# 08_Peripherals.net
KiCad netlist of a schematic drawn in Altium Designer
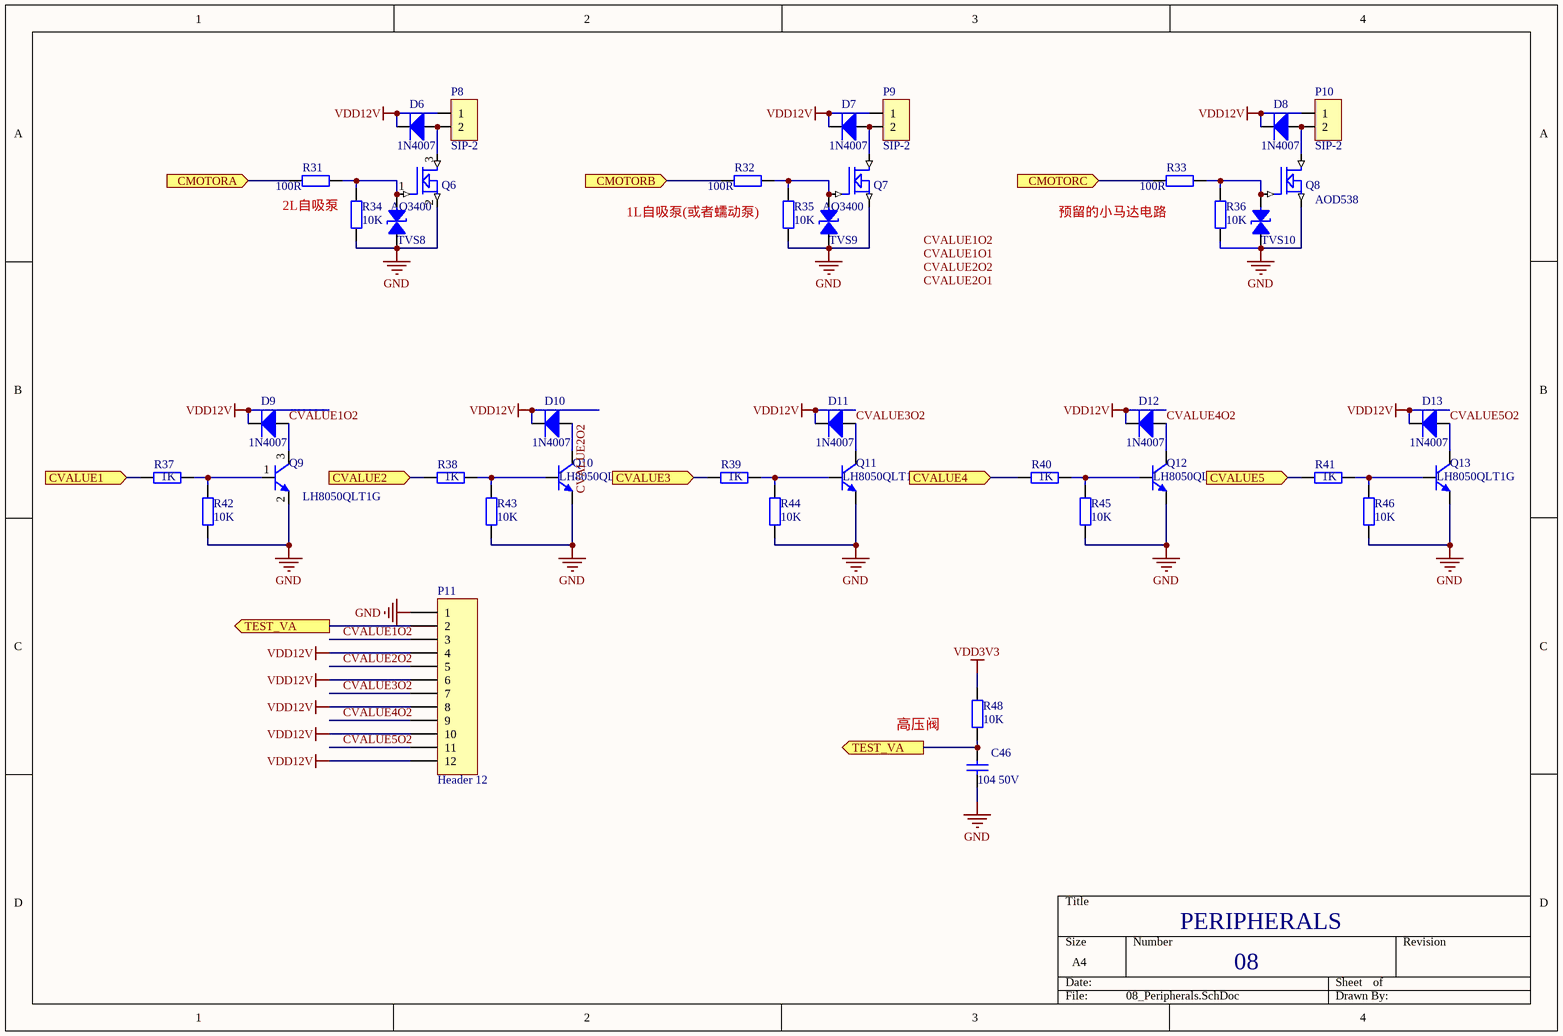
[diagram p0: 08_Peripherals.SchDoc]

(export (version "E")
  (design (tool "Eeschema 10.0.6"))
  (components
    (comp (ref "C46")
      (value "104 50V")
      (footprint "SMD-0603C")
      (description "贴片电容 10%")
      (libsource (lib "XiaoyI") (part "CAP4"))
    )
    (comp (ref "D6")
      (value "1N4007")
      (footprint "DO-214-AC")
      (description "贴片二极管")
      (libsource (lib "XiaoyI") (part "DIODE2"))
    )
    (comp (ref "D7")
      (value "1N4007")
      (footprint "DO-214-AC")
      (description "贴片二极管")
      (libsource (lib "XiaoyI") (part "DIODE2"))
    )
    (comp (ref "D8")
      (value "1N4007")
      (footprint "DO-214-AC")
      (description "贴片二极管")
      (libsource (lib "XiaoyI") (part "DIODE2"))
    )
    (comp (ref "D9")
      (value "1N4007")
      (footprint "DO-214-AC")
      (description "贴片二极管")
      (libsource (lib "XiaoyI") (part "DIODE2"))
    )
    (comp (ref "D10")
      (value "1N4007")
      (footprint "DO-214-AC")
      (description "贴片二极管")
      (libsource (lib "XiaoyI") (part "DIODE2"))
    )
    (comp (ref "D11")
      (value "1N4007")
      (footprint "DO-214-AC")
      (description "贴片二极管")
      (libsource (lib "XiaoyI") (part "DIODE2"))
    )
    (comp (ref "D12")
      (value "1N4007")
      (footprint "DO-214-AC")
      (description "贴片二极管")
      (libsource (lib "XiaoyI") (part "DIODE2"))
    )
    (comp (ref "D13")
      (value "1N4007")
      (footprint "DO-214-AC")
      (description "贴片二极管")
      (libsource (lib "XiaoyI") (part "DIODE2"))
    )
    (comp (ref "P8")
      (value "SIP-2")
      (footprint "SIP-2A")
      (description "XH2.54 2P 立贴")
      (libsource (lib "XiaoyI") (part "SIP-2"))
    )
    (comp (ref "P9")
      (value "SIP-2")
      (footprint "SIP-2A")
      (description "XH2.54 2P 立贴")
      (libsource (lib "XiaoyI") (part "SIP-2"))
    )
    (comp (ref "P10")
      (value "SIP-2")
      (footprint "VH-AW-3.96*2P")
      (description "XH2.54 2P 立贴")
      (libsource (lib "XiaoyI") (part "SIP-2"))
    )
    (comp (ref "P11")
      (value "Header 12")
      (footprint "12X2.54MMZ")
      (description "Header, 12-Pin")
      (fields (field (name "PUBLISHER") "Altium Limited"))
      (libsource (lib "Miscellaneous Connectors") (part "Header 12"))
    )
    (comp (ref "Q6")
      (value "AO3400")
      (footprint "SOT-23")
      (description "MOSFET N")
      (libsource (lib "") (part "MOSFET N_1"))
    )
    (comp (ref "Q7")
      (value "AO3400")
      (footprint "SOT-23")
      (description "MOSFET N")
      (libsource (lib "XiaoyI") (part "MOSFET N"))
    )
    (comp (ref "Q8")
      (value "AOD538")
      (footprint "TO252")
      (description "MOSFET N")
      (libsource (lib "XiaoyI") (part "MOSFET N"))
    )
    (comp (ref "Q9")
      (value "LH8050QLT1G")
      (footprint "SOT-23")
      (description "三极管")
      (libsource (lib "") (part "NPN-1_1"))
    )
    (comp (ref "Q10")
      (value "LH8050QLT1G")
      (footprint "SOT-23")
      (description "三极管")
      (libsource (lib "XiaoyI") (part "NPN-1"))
    )
    (comp (ref "Q11")
      (value "LH8050QLT1G")
      (footprint "SOT-23")
      (description "三极管")
      (libsource (lib "XiaoyI") (part "NPN-1"))
    )
    (comp (ref "Q12")
      (value "LH8050QLT1G")
      (footprint "SOT-23")
      (description "三极管")
      (libsource (lib "XiaoyI") (part "NPN-1"))
    )
    (comp (ref "Q13")
      (value "LH8050QLT1G")
      (footprint "SOT-23")
      (description "三极管")
      (libsource (lib "XiaoyI") (part "NPN-1"))
    )
    (comp (ref "R31")
      (value "100R")
      (footprint "SMD-0603")
      (description "贴片电阻 5%")
      (libsource (lib "XiaoyI") (part "RES-SOP"))
    )
    (comp (ref "R32")
      (value "100R")
      (footprint "SMD-0603")
      (description "贴片电阻 5%")
      (libsource (lib "XiaoyI") (part "RES-SOP"))
    )
    (comp (ref "R33")
      (value "100R")
      (footprint "SMD-0603")
      (description "贴片电阻 5%")
      (libsource (lib "XiaoyI") (part "RES-SOP"))
    )
    (comp (ref "R34")
      (value "10K")
      (footprint "SMD-0603")
      (description "贴片电阻 5%")
      (libsource (lib "") (part "RES-SOP_1"))
    )
    (comp (ref "R35")
      (value "10K")
      (footprint "SMD-0603")
      (description "贴片电阻 5%")
      (libsource (lib "") (part "RES-SOP_1"))
    )
    (comp (ref "R36")
      (value "10K")
      (footprint "SMD-0603")
      (description "贴片电阻 5%")
      (libsource (lib "") (part "RES-SOP_1"))
    )
    (comp (ref "R37")
      (value "1K")
      (footprint "SMD-0603")
      (description "贴片电阻 5%")
      (libsource (lib "XiaoyI") (part "RES-SOP"))
    )
    (comp (ref "R38")
      (value "1K")
      (footprint "SMD-0603")
      (description "贴片电阻 5%")
      (libsource (lib "XiaoyI") (part "RES-SOP"))
    )
    (comp (ref "R39")
      (value "1K")
      (footprint "SMD-0603")
      (description "贴片电阻 5%")
      (libsource (lib "XiaoyI") (part "RES-SOP"))
    )
    (comp (ref "R40")
      (value "1K")
      (footprint "SMD-0603")
      (description "贴片电阻 5%")
      (libsource (lib "XiaoyI") (part "RES-SOP"))
    )
    (comp (ref "R41")
      (value "1K")
      (footprint "SMD-0603")
      (description "贴片电阻 5%")
      (libsource (lib "XiaoyI") (part "RES-SOP"))
    )
    (comp (ref "R42")
      (value "10K")
      (footprint "SMD-0603")
      (description "贴片电阻 5%")
      (libsource (lib "") (part "RES-SOP_1"))
    )
    (comp (ref "R43")
      (value "10K")
      (footprint "SMD-0603")
      (description "贴片电阻 5%")
      (libsource (lib "") (part "RES-SOP_1"))
    )
    (comp (ref "R44")
      (value "10K")
      (footprint "SMD-0603")
      (description "贴片电阻 5%")
      (libsource (lib "") (part "RES-SOP_1"))
    )
    (comp (ref "R45")
      (value "10K")
      (footprint "SMD-0603")
      (description "贴片电阻 5%")
      (libsource (lib "") (part "RES-SOP_1"))
    )
    (comp (ref "R46")
      (value "10K")
      (footprint "SMD-0603")
      (description "贴片电阻 5%")
      (libsource (lib "") (part "RES-SOP_1"))
    )
    (comp (ref "R48")
      (value "10K")
      (footprint "SMD-0603")
      (description "贴片电阻 5%")
      (libsource (lib "") (part "RES-SOP_2"))
    )
    (comp (ref "TVS8")
      (value "ESD5Z5.0CT1G")
      (footprint "SOD-523")
      (description "TVS")
      (libsource (lib "XiaoyI") (part "TVS-1"))
    )
    (comp (ref "TVS9")
      (value "ESD5Z5.0CT1G")
      (footprint "SOD-523")
      (description "TVS")
      (libsource (lib "XiaoyI") (part "TVS-1"))
    )
    (comp (ref "TVS10")
      (value "ESD5Z5.0CT1G")
      (footprint "SOD-523")
      (description "TVS")
      (libsource (lib "XiaoyI") (part "TVS-1"))
    )
  )
  (nets
    (net (code "1") (name "/CMOTORA") (class "Default")
      (node (ref "R31") (pin "2") (pinfunction "2_2") (pintype "passive"))
    )
    (net (code "2") (name "/CMOTORB") (class "Default")
      (node (ref "R32") (pin "2") (pinfunction "2_2") (pintype "passive"))
    )
    (net (code "3") (name "/CMOTORC") (class "Default")
      (node (ref "R33") (pin "2") (pinfunction "2_2") (pintype "passive"))
    )
    (net (code "4") (name "/CVALUE1") (class "Default")
      (node (ref "R37") (pin "2") (pinfunction "2_2") (pintype "passive"))
    )
    (net (code "6") (name "/CVALUE1O2") (class "Default")
      (node (ref "D9") (pin "1") (pinfunction "A_1") (pintype "passive"))
      (node (ref "P11") (pin "3") (pinfunction "3_3") (pintype "passive"))
      (node (ref "Q9") (pin "3") (pinfunction "C_3") (pintype "passive"))
    )
    (net (code "7") (name "/CVALUE2") (class "Default")
      (node (ref "R38") (pin "2") (pinfunction "2_2") (pintype "passive"))
    )
    (net (code "9") (name "/CVALUE2O2") (class "Default")
      (node (ref "D10") (pin "1") (pinfunction "A_1") (pintype "passive"))
      (node (ref "P11") (pin "5") (pinfunction "5_5") (pintype "passive"))
      (node (ref "Q10") (pin "3") (pinfunction "C_3") (pintype "passive"))
    )
    (net (code "10") (name "/CVALUE3") (class "Default")
      (node (ref "R39") (pin "2") (pinfunction "2_2") (pintype "passive"))
    )
    (net (code "11") (name "/CVALUE3O2") (class "Default")
      (node (ref "D11") (pin "1") (pinfunction "A_1") (pintype "passive"))
      (node (ref "P11") (pin "7") (pinfunction "7_7") (pintype "passive"))
      (node (ref "Q11") (pin "3") (pinfunction "C_3") (pintype "passive"))
    )
    (net (code "12") (name "/CVALUE4") (class "Default")
      (node (ref "R40") (pin "2") (pinfunction "2_2") (pintype "passive"))
    )
    (net (code "13") (name "/CVALUE4O2") (class "Default")
      (node (ref "D12") (pin "1") (pinfunction "A_1") (pintype "passive"))
      (node (ref "P11") (pin "9") (pinfunction "9_9") (pintype "passive"))
      (node (ref "Q12") (pin "3") (pinfunction "C_3") (pintype "passive"))
    )
    (net (code "14") (name "/CVALUE5") (class "Default")
      (node (ref "R41") (pin "2") (pinfunction "2_2") (pintype "passive"))
    )
    (net (code "15") (name "/CVALUE5O2") (class "Default")
      (node (ref "D13") (pin "1") (pinfunction "A_1") (pintype "passive"))
      (node (ref "P11") (pin "11") (pinfunction "11_11") (pintype "passive"))
      (node (ref "Q13") (pin "3") (pinfunction "C_3") (pintype "passive"))
    )
    (net (code "16") (name "/TEST_VA") (class "Default")
      (node (ref "C46") (pin "2") (pinfunction "2_2") (pintype "passive"))
      (node (ref "P11") (pin "2") (pinfunction "2_2") (pintype "passive"))
      (node (ref "R48") (pin "1") (pinfunction "1_1") (pintype "passive"))
    )
    (net (code "17") (name "GND") (class "Default")
      (node (ref "C46") (pin "1") (pinfunction "1_1") (pintype "passive"))
      (node (ref "P11") (pin "1") (pinfunction "1_1") (pintype "passive"))
      (node (ref "Q10") (pin "2") (pinfunction "E_2") (pintype "passive"))
      (node (ref "Q11") (pin "2") (pinfunction "E_2") (pintype "passive"))
      (node (ref "Q12") (pin "2") (pinfunction "E_2") (pintype "passive"))
      (node (ref "Q13") (pin "2") (pinfunction "E_2") (pintype "passive"))
      (node (ref "Q6") (pin "2") (pinfunction "S_2") (pintype "output"))
      (node (ref "Q7") (pin "2") (pinfunction "S_2") (pintype "output"))
      (node (ref "Q8") (pin "2") (pinfunction "S_2") (pintype "output"))
      (node (ref "Q9") (pin "2") (pinfunction "E_2") (pintype "passive"))
      (node (ref "R34") (pin "2") (pinfunction "2_2") (pintype "passive"))
      (node (ref "R35") (pin "2") (pinfunction "2_2") (pintype "passive"))
      (node (ref "R36") (pin "2") (pinfunction "2_2") (pintype "passive"))
      (node (ref "R42") (pin "2") (pinfunction "2_2") (pintype "passive"))
      (node (ref "R43") (pin "2") (pinfunction "2_2") (pintype "passive"))
      (node (ref "R44") (pin "2") (pinfunction "2_2") (pintype "passive"))
      (node (ref "R45") (pin "2") (pinfunction "2_2") (pintype "passive"))
      (node (ref "R46") (pin "2") (pinfunction "2_2") (pintype "passive"))
      (node (ref "TVS10") (pin "1") (pinfunction "A_1") (pintype "passive"))
      (node (ref "TVS8") (pin "1") (pinfunction "A_1") (pintype "passive"))
      (node (ref "TVS9") (pin "1") (pinfunction "A_1") (pintype "passive"))
    )
    (net (code "18") (name "Net-(D6-A)") (class "Default")
      (node (ref "D6") (pin "1") (pinfunction "A_1") (pintype "passive"))
      (node (ref "P8") (pin "2") (pinfunction "2_2") (pintype "passive"))
      (node (ref "Q6") (pin "3") (pinfunction "D_3") (pintype "input"))
    )
    (net (code "19") (name "Net-(D7-A)") (class "Default")
      (node (ref "D7") (pin "1") (pinfunction "A_1") (pintype "passive"))
      (node (ref "P9") (pin "2") (pinfunction "2_2") (pintype "passive"))
      (node (ref "Q7") (pin "3") (pinfunction "D_3") (pintype "input"))
    )
    (net (code "20") (name "Net-(D8-A)") (class "Default")
      (node (ref "D8") (pin "1") (pinfunction "A_1") (pintype "passive"))
      (node (ref "P10") (pin "2") (pinfunction "2_2") (pintype "passive"))
      (node (ref "Q8") (pin "3") (pinfunction "D_3") (pintype "input"))
    )
    (net (code "21") (name "Net-(Q6-G)") (class "Default")
      (node (ref "Q6") (pin "1") (pinfunction "G_1") (pintype "input"))
      (node (ref "R31") (pin "1") (pinfunction "1_1") (pintype "passive"))
      (node (ref "R34") (pin "1") (pinfunction "1_1") (pintype "passive"))
      (node (ref "TVS8") (pin "2") (pinfunction "B_2") (pintype "passive"))
    )
    (net (code "22") (name "Net-(Q7-G)") (class "Default")
      (node (ref "Q7") (pin "1") (pinfunction "G_1") (pintype "input"))
      (node (ref "R32") (pin "1") (pinfunction "1_1") (pintype "passive"))
      (node (ref "R35") (pin "1") (pinfunction "1_1") (pintype "passive"))
      (node (ref "TVS9") (pin "2") (pinfunction "B_2") (pintype "passive"))
    )
    (net (code "23") (name "Net-(Q8-G)") (class "Default")
      (node (ref "Q8") (pin "1") (pinfunction "G_1") (pintype "input"))
      (node (ref "R33") (pin "1") (pinfunction "1_1") (pintype "passive"))
      (node (ref "R36") (pin "1") (pinfunction "1_1") (pintype "passive"))
      (node (ref "TVS10") (pin "2") (pinfunction "B_2") (pintype "passive"))
    )
    (net (code "24") (name "Net-(Q9-B)") (class "Default")
      (node (ref "Q9") (pin "1") (pinfunction "B_1") (pintype "passive"))
      (node (ref "R37") (pin "1") (pinfunction "1_1") (pintype "passive"))
      (node (ref "R42") (pin "1") (pinfunction "1_1") (pintype "passive"))
    )
    (net (code "25") (name "Net-(Q10-B)") (class "Default")
      (node (ref "Q10") (pin "1") (pinfunction "B_1") (pintype "passive"))
      (node (ref "R38") (pin "1") (pinfunction "1_1") (pintype "passive"))
      (node (ref "R43") (pin "1") (pinfunction "1_1") (pintype "passive"))
    )
    (net (code "26") (name "Net-(Q11-B)") (class "Default")
      (node (ref "Q11") (pin "1") (pinfunction "B_1") (pintype "passive"))
      (node (ref "R39") (pin "1") (pinfunction "1_1") (pintype "passive"))
      (node (ref "R44") (pin "1") (pinfunction "1_1") (pintype "passive"))
    )
    (net (code "27") (name "Net-(Q12-B)") (class "Default")
      (node (ref "Q12") (pin "1") (pinfunction "B_1") (pintype "passive"))
      (node (ref "R40") (pin "1") (pinfunction "1_1") (pintype "passive"))
      (node (ref "R45") (pin "1") (pinfunction "1_1") (pintype "passive"))
    )
    (net (code "28") (name "Net-(Q13-B)") (class "Default")
      (node (ref "Q13") (pin "1") (pinfunction "B_1") (pintype "passive"))
      (node (ref "R41") (pin "1") (pinfunction "1_1") (pintype "passive"))
      (node (ref "R46") (pin "1") (pinfunction "1_1") (pintype "passive"))
    )
    (net (code "29") (name "VDD3V3") (class "Default")
      (node (ref "R48") (pin "2") (pinfunction "2_2") (pintype "passive"))
    )
    (net (code "30") (name "VDD12V") (class "Default")
      (node (ref "D10") (pin "2") (pinfunction "K_2") (pintype "passive"))
      (node (ref "D11") (pin "2") (pinfunction "K_2") (pintype "passive"))
      (node (ref "D12") (pin "2") (pinfunction "K_2") (pintype "passive"))
      (node (ref "D13") (pin "2") (pinfunction "K_2") (pintype "passive"))
      (node (ref "D6") (pin "2") (pinfunction "K_2") (pintype "passive"))
      (node (ref "D7") (pin "2") (pinfunction "K_2") (pintype "passive"))
      (node (ref "D8") (pin "2") (pinfunction "K_2") (pintype "passive"))
      (node (ref "D9") (pin "2") (pinfunction "K_2") (pintype "passive"))
      (node (ref "P10") (pin "1") (pinfunction "1_1") (pintype "passive"))
      (node (ref "P11") (pin "10") (pinfunction "10_10") (pintype "passive"))
      (node (ref "P11") (pin "12") (pinfunction "12_12") (pintype "passive"))
      (node (ref "P11") (pin "4") (pinfunction "4_4") (pintype "passive"))
      (node (ref "P11") (pin "6") (pinfunction "6_6") (pintype "passive"))
      (node (ref "P11") (pin "8") (pinfunction "8_8") (pintype "passive"))
      (node (ref "P8") (pin "1") (pinfunction "1_1") (pintype "passive"))
      (node (ref "P9") (pin "1") (pinfunction "1_1") (pintype "passive"))
    )
  )
)
